# Schematic_Ebook_Reader_vFinal_v33.net
KiCad netlist of a schematic drawn in EAGLE
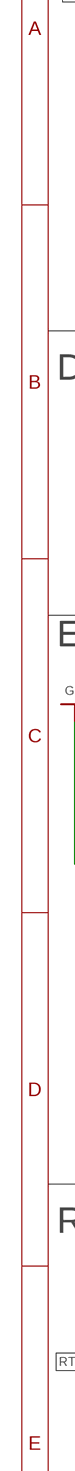
[diagram p0: schematic, sheet 1, part 1 of 2]
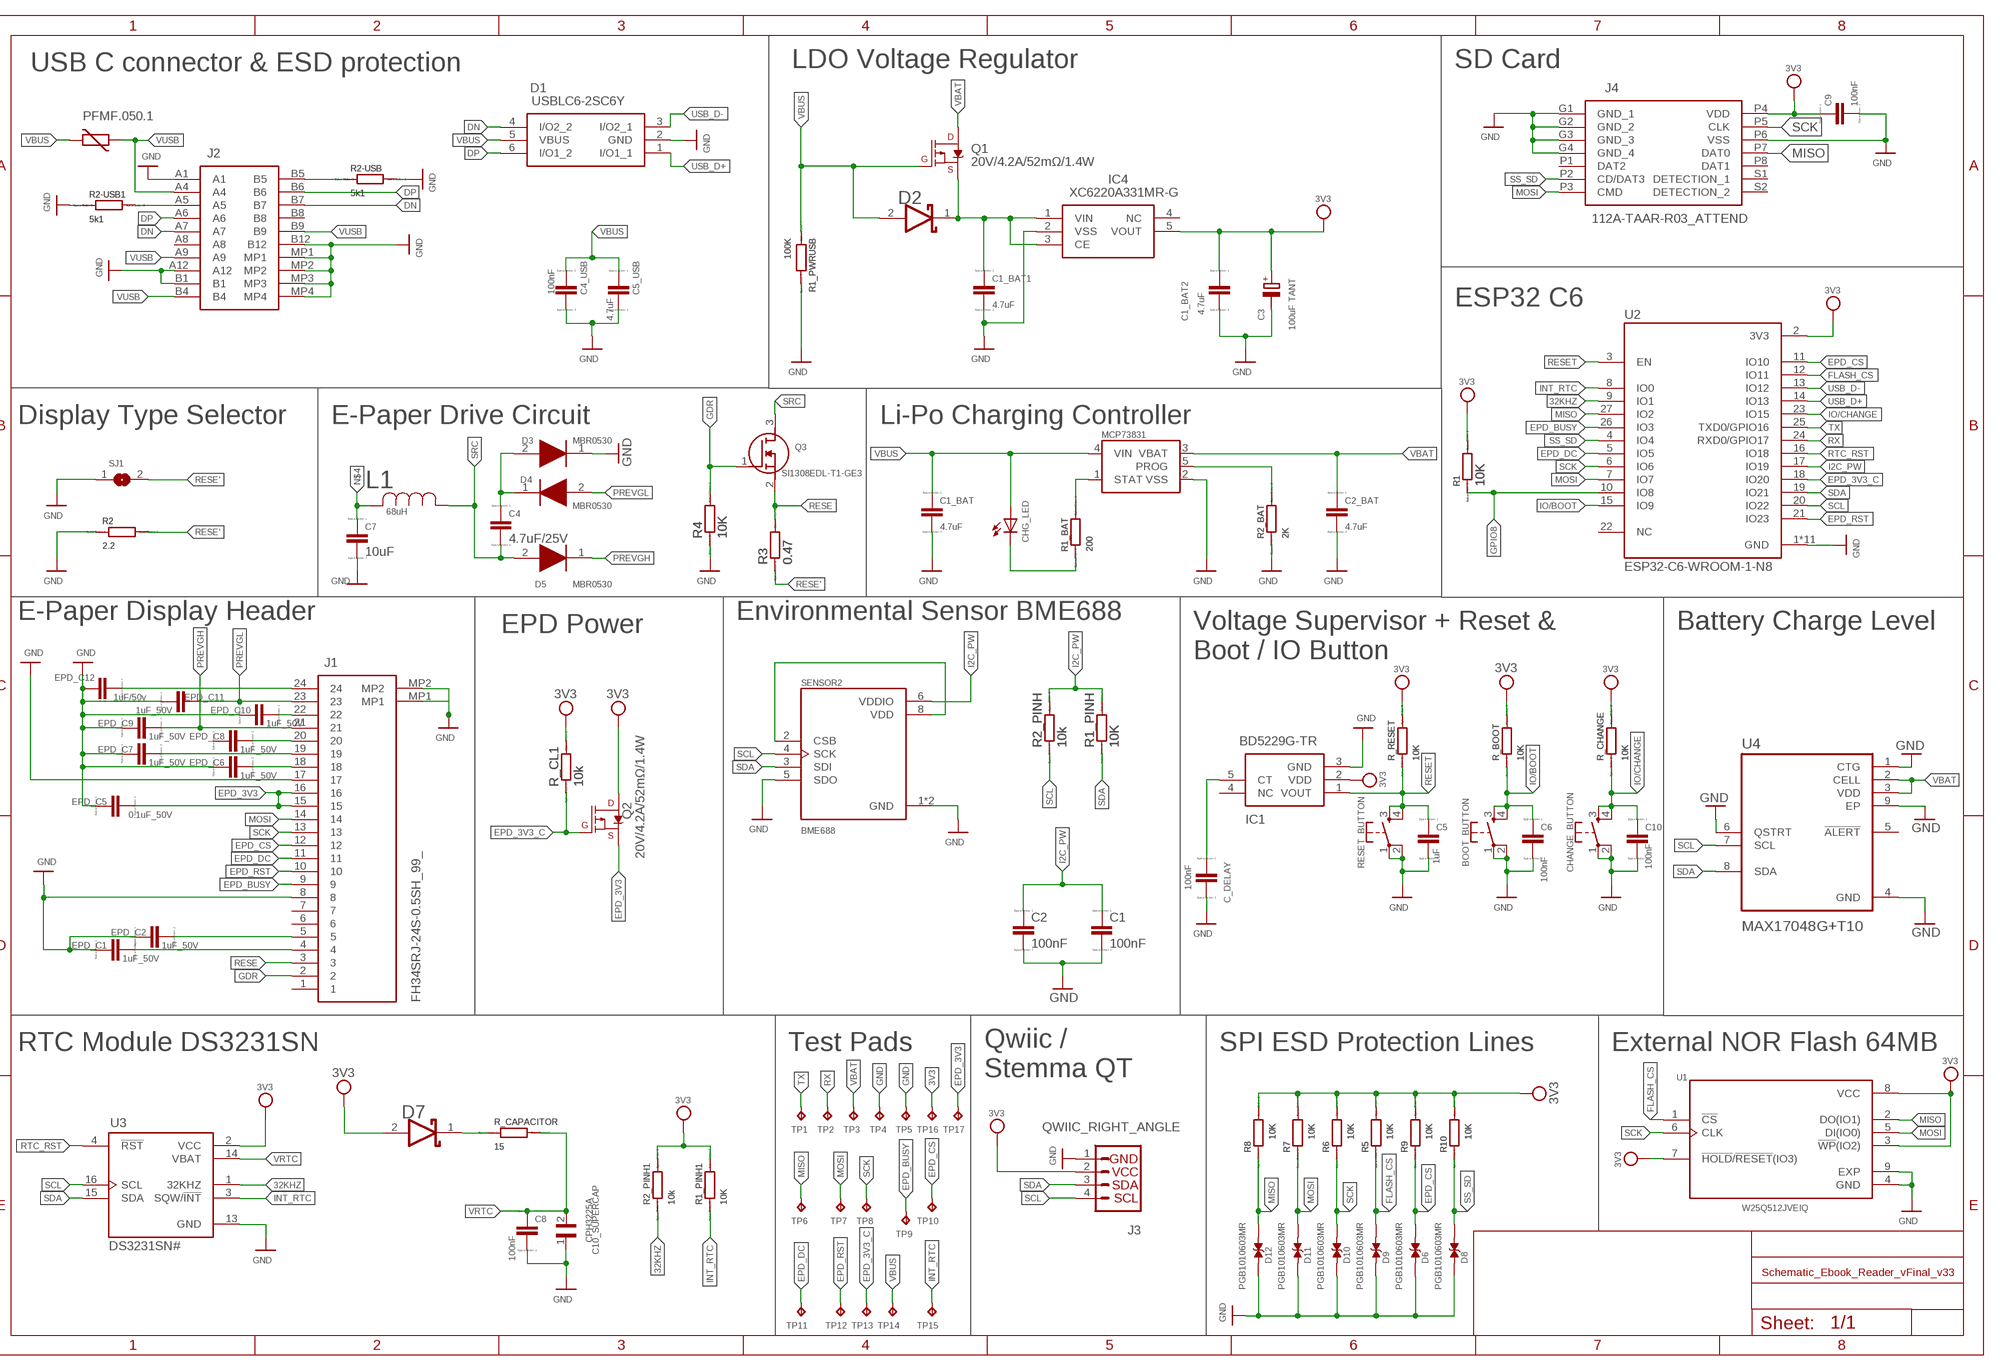
[diagram p1: schematic, sheet 1, part 2 of 2]

(export (version "E")
  (design (tool "Eeschema 10.0.6"))
  (components
    (comp (ref "BOOT_BUTTON")
      (value "BUTTON_CUSYOMV1")
      (footprint "eagle-import:MYBUTTON")
      (libsource (lib "eagle-import") (part "BUTTON_CUSYOMV1"))
    )
    (comp (ref "C1")
      (value "100nF")
      (footprint "eagle-import:EAGLE-LTSPICE_C0402")
      (libsource (lib "eagle-import") (part "EAGLE-LTSPICE_CC0402"))
    )
    (comp (ref "C1_BAT")
      (value "4.7uF")
      (footprint "eagle-import:EAGLE-LTSPICE_C0402")
      (libsource (lib "eagle-import") (part "EAGLE-LTSPICE_CC0402"))
    )
    (comp (ref "C1_BAT1")
      (value "4.7uF")
      (footprint "eagle-import:EAGLE-LTSPICE_C0402")
      (libsource (lib "eagle-import") (part "EAGLE-LTSPICE_CC0402"))
    )
    (comp (ref "C1_BAT2")
      (value "4.7uF")
      (footprint "eagle-import:EAGLE-LTSPICE_C0402")
      (libsource (lib "eagle-import") (part "EAGLE-LTSPICE_CC0402"))
    )
    (comp (ref "C2")
      (value "100nF")
      (footprint "eagle-import:EAGLE-LTSPICE_C0402")
      (libsource (lib "eagle-import") (part "EAGLE-LTSPICE_CC0402"))
    )
    (comp (ref "C2_BAT")
      (value "4.7uF")
      (footprint "eagle-import:EAGLE-LTSPICE_C0402")
      (libsource (lib "eagle-import") (part "EAGLE-LTSPICE_CC0402"))
    )
    (comp (ref "C3")
      (value "100uF TANT")
      (footprint "eagle-import:RCL_CT3528")
      (libsource (lib "eagle-import") (part "RCL_CPOL-EUCT3528"))
    )
    (comp (ref "C4")
      (value "4.7uF/25V")
      (footprint "eagle-import:EAGLE-LTSPICE_C0402")
      (libsource (lib "eagle-import") (part "EAGLE-LTSPICE_CC0402"))
    )
    (comp (ref "C4_USB")
      (value "100nF")
      (footprint "eagle-import:EAGLE-LTSPICE_C0402")
      (libsource (lib "eagle-import") (part "EAGLE-LTSPICE_CC0402"))
    )
    (comp (ref "C5")
      (value "1uF")
      (footprint "eagle-import:EAGLE-LTSPICE_C0402")
      (libsource (lib "eagle-import") (part "EAGLE-LTSPICE_CC0402"))
    )
    (comp (ref "C5_USB")
      (value "4.7uF")
      (footprint "eagle-import:EAGLE-LTSPICE_C0402")
      (libsource (lib "eagle-import") (part "EAGLE-LTSPICE_CC0402"))
    )
    (comp (ref "C6")
      (value "100nF")
      (footprint "eagle-import:EAGLE-LTSPICE_C0402")
      (libsource (lib "eagle-import") (part "EAGLE-LTSPICE_CC0402"))
    )
    (comp (ref "C7")
      (value "10uF")
      (footprint "eagle-import:EAGLE-LTSPICE_C0402")
      (libsource (lib "eagle-import") (part "EAGLE-LTSPICE_CC0402"))
    )
    (comp (ref "C8")
      (value "100nF")
      (footprint "eagle-import:EAGLE-LTSPICE_C0402")
      (libsource (lib "eagle-import") (part "EAGLE-LTSPICE_CC0402"))
    )
    (comp (ref "C9")
      (value "100nF")
      (footprint "eagle-import:EAGLE-LTSPICE_C0402")
      (libsource (lib "eagle-import") (part "EAGLE-LTSPICE_CC0402"))
    )
    (comp (ref "C10")
      (value "100nF")
      (footprint "eagle-import:EAGLE-LTSPICE_C0402")
      (libsource (lib "eagle-import") (part "EAGLE-LTSPICE_CC0402"))
    )
    (comp (ref "C10_SUPERCAP")
      (value "CPH3225A")
      (footprint "eagle-import:CAPCP3225X100N")
      (fields (field (name "MF") "Seiko Instruments"))
      (libsource (lib "eagle-import") (part "CPH3225A"))
    )
    (comp (ref "CHANGE_BUTTON")
      (value "BUTTON_CUSYOMV1")
      (footprint "eagle-import:MYBUTTON")
      (libsource (lib "eagle-import") (part "BUTTON_CUSYOMV1"))
    )
    (comp (ref "CHG_LED")
      (value "ADAFRUIT_LEDCHIP-LED0603")
      (footprint "eagle-import:ADAFRUIT_CHIP-LED0603")
      (libsource (lib "eagle-import") (part "ADAFRUIT_LEDCHIP-LED0603"))
    )
    (comp (ref "C_DELAY")
      (value "100nF")
      (footprint "eagle-import:EAGLE-LTSPICE_C0402")
      (libsource (lib "eagle-import") (part "EAGLE-LTSPICE_CC0402"))
    )
    (comp (ref "D1")
      (value "USBLC6-2SC6Y")
      (footprint "eagle-import:SOT95P280X145-6N")
      (fields (field (name "MF") "STMicroelectronics"))
      (libsource (lib "eagle-import") (part "USBLC6-2SC6Y"))
    )
    (comp (ref "D2")
      (value "ESP32_WROVER_AVX---SD0805S020S1R0_AVX_SD0805S020S1R0_0_0AVX_SD0805S020S1R0_0_0")
      (footprint "eagle-import:ESP32_WROVER_AVX---SD0805S020S1R0_AVX_SD0805S020S1R0_0")
      (fields
        (field (name "DIGIKEY_PART_NUMBER") "478-7800-1-ND")
        (field (name "MF") "AVX")
        (field (name "MOUSER_PART_NUMBER") "581-SD0805S020S1R0")
      )
      (libsource (lib "eagle-import") (part "ESP32_WROVER_AVX---SD0805S020S1R0_AVX_SD0805S020S1R0_0_0AVX_SD0805S020S1R0_0_0"))
    )
    (comp (ref "D3")
      (value "MBR0530")
      (footprint "eagle-import:SOD3716X135N")
      (fields (field (name "MF") "ON Semiconductor"))
      (libsource (lib "eagle-import") (part "MBR0530"))
    )
    (comp (ref "D4")
      (value "MBR0530")
      (footprint "eagle-import:SOD3716X135N")
      (fields (field (name "MF") "ON Semiconductor"))
      (libsource (lib "eagle-import") (part "MBR0530"))
    )
    (comp (ref "D5")
      (value "MBR0530")
      (footprint "eagle-import:SOD3716X135N")
      (fields (field (name "MF") "ON Semiconductor"))
      (libsource (lib "eagle-import") (part "MBR0530"))
    )
    (comp (ref "D6")
      (value "PGB1010603MR")
      (footprint "eagle-import:DIOC1608X36N")
      (fields (field (name "MF") "Littelfuse Inc."))
      (libsource (lib "eagle-import") (part "PGB1010603MR"))
    )
    (comp (ref "D7")
      (value "ESP32_WROVER_AVX---SD0805S020S1R0_AVX_SD0805S020S1R0_0_0AVX_SD0805S020S1R0_0_0")
      (footprint "eagle-import:ESP32_WROVER_AVX---SD0805S020S1R0_AVX_SD0805S020S1R0_0")
      (fields
        (field (name "DIGIKEY_PART_NUMBER") "478-7800-1-ND")
        (field (name "MF") "AVX")
        (field (name "MOUSER_PART_NUMBER") "581-SD0805S020S1R0")
      )
      (libsource (lib "eagle-import") (part "ESP32_WROVER_AVX---SD0805S020S1R0_AVX_SD0805S020S1R0_0_0AVX_SD0805S020S1R0_0_0"))
    )
    (comp (ref "D8")
      (value "PGB1010603MR")
      (footprint "eagle-import:DIOC1608X36N")
      (fields (field (name "MF") "Littelfuse Inc."))
      (libsource (lib "eagle-import") (part "PGB1010603MR"))
    )
    (comp (ref "D9")
      (value "PGB1010603MR")
      (footprint "eagle-import:DIOC1608X36N")
      (fields (field (name "MF") "Littelfuse Inc."))
      (libsource (lib "eagle-import") (part "PGB1010603MR"))
    )
    (comp (ref "D10")
      (value "PGB1010603MR")
      (footprint "eagle-import:DIOC1608X36N")
      (fields (field (name "MF") "Littelfuse Inc."))
      (libsource (lib "eagle-import") (part "PGB1010603MR"))
    )
    (comp (ref "D11")
      (value "PGB1010603MR")
      (footprint "eagle-import:DIOC1608X36N")
      (fields (field (name "MF") "Littelfuse Inc."))
      (libsource (lib "eagle-import") (part "PGB1010603MR"))
    )
    (comp (ref "D12")
      (value "PGB1010603MR")
      (footprint "eagle-import:DIOC1608X36N")
      (fields (field (name "MF") "Littelfuse Inc."))
      (libsource (lib "eagle-import") (part "PGB1010603MR"))
    )
    (comp (ref "EPD_C1")
      (value "1uF_50V")
      (footprint "eagle-import:EAGLE-LTSPICE_C0402")
      (libsource (lib "eagle-import") (part "EAGLE-LTSPICE_CC0402"))
    )
    (comp (ref "EPD_C2")
      (value "1uF_50V")
      (footprint "eagle-import:EAGLE-LTSPICE_C0402")
      (libsource (lib "eagle-import") (part "EAGLE-LTSPICE_CC0402"))
    )
    (comp (ref "EPD_C5")
      (value "0.1uF_50V")
      (footprint "eagle-import:EAGLE-LTSPICE_C0402")
      (libsource (lib "eagle-import") (part "EAGLE-LTSPICE_CC0402"))
    )
    (comp (ref "EPD_C6")
      (value "1uF_50V")
      (footprint "eagle-import:EAGLE-LTSPICE_C0402")
      (libsource (lib "eagle-import") (part "EAGLE-LTSPICE_CC0402"))
    )
    (comp (ref "EPD_C7")
      (value "1uF_50V")
      (footprint "eagle-import:EAGLE-LTSPICE_C0402")
      (libsource (lib "eagle-import") (part "EAGLE-LTSPICE_CC0402"))
    )
    (comp (ref "EPD_C8")
      (value "1uF_50V")
      (footprint "eagle-import:EAGLE-LTSPICE_C0402")
      (libsource (lib "eagle-import") (part "EAGLE-LTSPICE_CC0402"))
    )
    (comp (ref "EPD_C9")
      (value "1uF_50V")
      (footprint "eagle-import:EAGLE-LTSPICE_C0402")
      (libsource (lib "eagle-import") (part "EAGLE-LTSPICE_CC0402"))
    )
    (comp (ref "EPD_C10")
      (value "1uF_50V")
      (footprint "eagle-import:EAGLE-LTSPICE_C0402")
      (libsource (lib "eagle-import") (part "EAGLE-LTSPICE_CC0402"))
    )
    (comp (ref "EPD_C11")
      (value "1uF_50V")
      (footprint "eagle-import:EAGLE-LTSPICE_C0402")
      (libsource (lib "eagle-import") (part "EAGLE-LTSPICE_CC0402"))
    )
    (comp (ref "EPD_C12")
      (value "1uF/50v")
      (footprint "eagle-import:EAGLE-LTSPICE_C0402")
      (libsource (lib "eagle-import") (part "EAGLE-LTSPICE_CC0402"))
    )
    (comp (ref "IC1")
      (value "BD5229G-TR")
      (footprint "eagle-import:SOT95P280X125-5N")
      (fields (field (name "MOUSER_PART_NUMBER") "755-BD5229G-TR"))
      (libsource (lib "eagle-import") (part "BD5229G-TR"))
    )
    (comp (ref "IC4")
      (value "XC6220A331MR-G")
      (footprint "eagle-import:SOT95P280X120-5N")
      (fields (field (name "MOUSER_PART_NUMBER") "865-XC6220A331MR-G"))
      (libsource (lib "eagle-import") (part "XC6220A331MR-G"))
    )
    (comp (ref "J1")
      (value "FH34SRJ-24S-0.5SH_99_")
      (footprint "eagle-import:FH34SRJ24S05SH99")
      (fields
        (field (name "MANUFACTURER_PART_NUMBER") "FH34SRJ-24S-0.5SH(99)")
        (field (name "MOUSER_PART_NUMBER") "798-FH34SRJ24S05SH99")
      )
      (libsource (lib "eagle-import") (part "FH34SRJ-24S-0.5SH_99_"))
    )
    (comp (ref "J2")
      (value "SAMACSYS_PARTS_USB4110-GF-A")
      (footprint "eagle-import:SAMACSYS_PARTS_USB4110GFA")
      (fields
        (field (name "MANUFACTURER_PART_NUMBER") "USB4110-GF-A")
        (field (name "MOUSER_PART_NUMBER") "640-USB4110-GF-A")
      )
      (libsource (lib "eagle-import") (part "SAMACSYS_PARTS_USB4110-GF-A"))
    )
    (comp (ref "J3")
      (value "QWIIC_RIGHT_ANGLE")
      (footprint "eagle-import:JST04_1MM_RA")
      (libsource (lib "eagle-import") (part "QWIIC_CONNECTORJS-1MM"))
    )
    (comp (ref "J4")
      (value "112A-TAAR-R03_ATTEND")
      (footprint "eagle-import:112ATAARR03ATTEND")
      (fields (field (name "MANUFACTURER_PART_NUMBER") "112A-TAAR-R03 ATTEND"))
      (libsource (lib "eagle-import") (part "112A-TAAR-R03_ATTEND"))
    )
    (comp (ref "L1")
      (value "68uH")
      (footprint "eagle-import:IND_4828-WE-TPC_WRE")
      (fields
        (field (name "MANUFACTURER_PART_NUMBER") "744043680")
        (field (name "COPYRIGHT") "Copyright (C) 2024 Ultra Librarian. All rights reserved.")
      )
      (libsource (lib "eagle-import") (part "744043680IND_4828-WE-TPC_WRE"))
    )
    (comp (ref "MCP73831")
      (value "ESP32_WROVER_SPARKFUN-IC-POWER_MCP73831")
      (footprint "eagle-import:ESP32_WROVER_SPARKFUN-IC-POWER_SOT23-5")
      (libsource (lib "eagle-import") (part "ESP32_WROVER_SPARKFUN-IC-POWER_MCP73831"))
    )
    (comp (ref "PFMF.050.1")
      (value "ESP32C6_VARISTORCN1812")
      (footprint "eagle-import:ESP32C6_VARISTOR_CT_CN1812")
      (libsource (lib "eagle-import") (part "ESP32C6_VARISTORCN1812"))
    )
    (comp (ref "Q1")
      (value "20V/4.2A/52mΩ/1.4W")
      (footprint "eagle-import:ESP32_WROVER_SPARKFUN-DISCRETESEMI_SOT23-3")
      (libsource (lib "eagle-import") (part "ESP32_WROVER_SPARKFUN-DISCRETESEMI_MOSFET_PCH-DMG2305UX-7"))
    )
    (comp (ref "Q2")
      (value "20V/4.2A/52mΩ/1.4W")
      (footprint "eagle-import:ESP32_WROVER_SPARKFUN-DISCRETESEMI_SOT23-3")
      (libsource (lib "eagle-import") (part "ESP32_WROVER_SPARKFUN-DISCRETESEMI_MOSFET_PCH-DMG2305UX-7"))
    )
    (comp (ref "Q3")
      (value "SI1308EDL-T1-GE3")
      (footprint "eagle-import:SOT65P210X110-3N")
      (fields (field (name "MF") "Vishay Siliconix"))
      (libsource (lib "eagle-import") (part "SI1308EDL-T1-GE3"))
    )
    (comp (ref "R1")
      (value "10K")
      (footprint "eagle-import:ESP32_WROVER_EAGLE-LTSPICE_R0402")
      (libsource (lib "eagle-import") (part "ESP32_WROVER_EAGLE-LTSPICE_RR0402"))
    )
    (comp (ref "R1_BAT")
      (value "200")
      (footprint "eagle-import:ESP32_WROVER_EAGLE-LTSPICE_R0402")
      (libsource (lib "eagle-import") (part "ESP32_WROVER_EAGLE-LTSPICE_RR0402"))
    )
    (comp (ref "R1_PINH")
      (value "10K")
      (footprint "eagle-import:ESP32_WROVER_EAGLE-LTSPICE_R0402")
      (libsource (lib "eagle-import") (part "ESP32_WROVER_EAGLE-LTSPICE_RR0402"))
    )
    (comp (ref "R1_PINH1")
      (value "10K")
      (footprint "eagle-import:ESP32_WROVER_EAGLE-LTSPICE_R0402")
      (libsource (lib "eagle-import") (part "ESP32_WROVER_EAGLE-LTSPICE_RR0402"))
    )
    (comp (ref "R1_PWRUSB")
      (value "100K")
      (footprint "eagle-import:ESP32_WROVER_EAGLE-LTSPICE_R0402")
      (libsource (lib "eagle-import") (part "ESP32_WROVER_EAGLE-LTSPICE_RR0402"))
    )
    (comp (ref "R2")
      (value "2.2")
      (footprint "eagle-import:ESP32_WROVER_EAGLE-LTSPICE_R0402")
      (libsource (lib "eagle-import") (part "ESP32_WROVER_EAGLE-LTSPICE_RR0402"))
    )
    (comp (ref "R2-USB")
      (value "5k1")
      (footprint "eagle-import:ESP32_WROVER_EAGLE-LTSPICE_R0402")
      (libsource (lib "eagle-import") (part "ESP32_WROVER_EAGLE-LTSPICE_RR0402"))
    )
    (comp (ref "R2-USB1")
      (value "5k1")
      (footprint "eagle-import:ESP32_WROVER_EAGLE-LTSPICE_R0402")
      (libsource (lib "eagle-import") (part "ESP32_WROVER_EAGLE-LTSPICE_RR0402"))
    )
    (comp (ref "R2_BAT")
      (value "2K")
      (footprint "eagle-import:ESP32_WROVER_EAGLE-LTSPICE_R0402")
      (libsource (lib "eagle-import") (part "ESP32_WROVER_EAGLE-LTSPICE_RR0402"))
    )
    (comp (ref "R2_PINH")
      (value "10k")
      (footprint "eagle-import:ESP32_WROVER_EAGLE-LTSPICE_R0402")
      (libsource (lib "eagle-import") (part "ESP32_WROVER_EAGLE-LTSPICE_RR0402"))
    )
    (comp (ref "R2_PINH1")
      (value "10k")
      (footprint "eagle-import:ESP32_WROVER_EAGLE-LTSPICE_R0402")
      (libsource (lib "eagle-import") (part "ESP32_WROVER_EAGLE-LTSPICE_RR0402"))
    )
    (comp (ref "R3")
      (value "0.47")
      (footprint "eagle-import:ESP32_WROVER_EAGLE-LTSPICE_R0402")
      (libsource (lib "eagle-import") (part "ESP32_WROVER_EAGLE-LTSPICE_RR0402"))
    )
    (comp (ref "R4")
      (value "10K")
      (footprint "eagle-import:ESP32_WROVER_EAGLE-LTSPICE_R0402")
      (libsource (lib "eagle-import") (part "ESP32_WROVER_EAGLE-LTSPICE_RR0402"))
    )
    (comp (ref "R5")
      (value "10K")
      (footprint "eagle-import:ESP32_WROVER_EAGLE-LTSPICE_R0402")
      (libsource (lib "eagle-import") (part "ESP32_WROVER_EAGLE-LTSPICE_RR0402"))
    )
    (comp (ref "R6")
      (value "10K")
      (footprint "eagle-import:ESP32_WROVER_EAGLE-LTSPICE_R0402")
      (libsource (lib "eagle-import") (part "ESP32_WROVER_EAGLE-LTSPICE_RR0402"))
    )
    (comp (ref "R7")
      (value "10K")
      (footprint "eagle-import:ESP32_WROVER_EAGLE-LTSPICE_R0402")
      (libsource (lib "eagle-import") (part "ESP32_WROVER_EAGLE-LTSPICE_RR0402"))
    )
    (comp (ref "R8")
      (value "10K")
      (footprint "eagle-import:ESP32_WROVER_EAGLE-LTSPICE_R0402")
      (libsource (lib "eagle-import") (part "ESP32_WROVER_EAGLE-LTSPICE_RR0402"))
    )
    (comp (ref "R9")
      (value "10K")
      (footprint "eagle-import:ESP32_WROVER_EAGLE-LTSPICE_R0402")
      (libsource (lib "eagle-import") (part "ESP32_WROVER_EAGLE-LTSPICE_RR0402"))
    )
    (comp (ref "R10")
      (value "10K")
      (footprint "eagle-import:ESP32_WROVER_EAGLE-LTSPICE_R0402")
      (libsource (lib "eagle-import") (part "ESP32_WROVER_EAGLE-LTSPICE_RR0402"))
    )
    (comp (ref "RESET_BUTTON")
      (value "BUTTON_CUSYOMV1")
      (footprint "eagle-import:MYBUTTON")
      (libsource (lib "eagle-import") (part "BUTTON_CUSYOMV1"))
    )
    (comp (ref "R_BOOT")
      (value "10K")
      (footprint "eagle-import:ESP32_WROVER_EAGLE-LTSPICE_R0402")
      (libsource (lib "eagle-import") (part "ESP32_WROVER_EAGLE-LTSPICE_RR0402"))
    )
    (comp (ref "R_CAPACITOR")
      (value "15")
      (footprint "eagle-import:ESP32_WROVER_EAGLE-LTSPICE_R0402")
      (libsource (lib "eagle-import") (part "ESP32_WROVER_EAGLE-LTSPICE_RR0402"))
    )
    (comp (ref "R_CHANGE")
      (value "10K")
      (footprint "eagle-import:ESP32_WROVER_EAGLE-LTSPICE_R0402")
      (libsource (lib "eagle-import") (part "ESP32_WROVER_EAGLE-LTSPICE_RR0402"))
    )
    (comp (ref "R_CL1")
      (value "10k")
      (footprint "eagle-import:ESP32_WROVER_EAGLE-LTSPICE_R0402")
      (libsource (lib "eagle-import") (part "ESP32_WROVER_EAGLE-LTSPICE_RR0402"))
    )
    (comp (ref "R_RESET")
      (value "10K")
      (footprint "eagle-import:ESP32_WROVER_EAGLE-LTSPICE_R0402")
      (libsource (lib "eagle-import") (part "ESP32_WROVER_EAGLE-LTSPICE_RR0402"))
    )
    (comp (ref "SENSOR2")
      (value "BME688")
      (footprint "eagle-import:ESP32_WROVER_BME680_PSON80P300X300X100-8N")
      (fields (field (name "MF") "Bosch Sensortec") (field (name "MP") "BME680"))
      (libsource (lib "eagle-import") (part "ESP32_WROVER_BME680_BME680"))
    )
    (comp (ref "SJ1") (value "SJ") (footprint "eagle-import:SJ") (libsource (lib "eagle-import") (part "SJ")))
    (comp (ref "TP1")
      (value "TPTP20R")
      (footprint "eagle-import:TP20R")
      (libsource (lib "eagle-import") (part "TPTP20R"))
    )
    (comp (ref "TP2")
      (value "TPTP20R")
      (footprint "eagle-import:TP20R")
      (libsource (lib "eagle-import") (part "TPTP20R"))
    )
    (comp (ref "TP3")
      (value "TPTP20R")
      (footprint "eagle-import:TP20R")
      (libsource (lib "eagle-import") (part "TPTP20R"))
    )
    (comp (ref "TP4")
      (value "TPTP20R")
      (footprint "eagle-import:TP20R")
      (libsource (lib "eagle-import") (part "TPTP20R"))
    )
    (comp (ref "TP5")
      (value "TPTP20R")
      (footprint "eagle-import:TP20R")
      (libsource (lib "eagle-import") (part "TPTP20R"))
    )
    (comp (ref "TP6")
      (value "TPTP20R")
      (footprint "eagle-import:TP20R")
      (libsource (lib "eagle-import") (part "TPTP20R"))
    )
    (comp (ref "TP7")
      (value "TPTP20R")
      (footprint "eagle-import:TP20R")
      (libsource (lib "eagle-import") (part "TPTP20R"))
    )
    (comp (ref "TP8")
      (value "TPTP20R")
      (footprint "eagle-import:TP20R")
      (libsource (lib "eagle-import") (part "TPTP20R"))
    )
    (comp (ref "TP9")
      (value "TPTP20R")
      (footprint "eagle-import:TP20R")
      (libsource (lib "eagle-import") (part "TPTP20R"))
    )
    (comp (ref "TP10")
      (value "TPTP20R")
      (footprint "eagle-import:TP20R")
      (libsource (lib "eagle-import") (part "TPTP20R"))
    )
    (comp (ref "TP11")
      (value "TPTP20R")
      (footprint "eagle-import:TP20R")
      (libsource (lib "eagle-import") (part "TPTP20R"))
    )
    (comp (ref "TP12")
      (value "TPTP20R")
      (footprint "eagle-import:TP20R")
      (libsource (lib "eagle-import") (part "TPTP20R"))
    )
    (comp (ref "TP13")
      (value "TPTP20R")
      (footprint "eagle-import:TP20R")
      (libsource (lib "eagle-import") (part "TPTP20R"))
    )
    (comp (ref "TP14")
      (value "TPTP20R")
      (footprint "eagle-import:TP20R")
      (libsource (lib "eagle-import") (part "TPTP20R"))
    )
    (comp (ref "TP15")
      (value "TPTP20R")
      (footprint "eagle-import:TP20R")
      (libsource (lib "eagle-import") (part "TPTP20R"))
    )
    (comp (ref "TP16")
      (value "TPTP20R")
      (footprint "eagle-import:TP20R")
      (libsource (lib "eagle-import") (part "TPTP20R"))
    )
    (comp (ref "TP17")
      (value "TPTP20R")
      (footprint "eagle-import:TP20R")
      (libsource (lib "eagle-import") (part "TPTP20R"))
    )
    (comp (ref "U1")
      (value "W25Q512JVEIQ")
      (footprint "eagle-import:SON127P600X800X80-9N")
      (fields (field (name "MF") "Winbond Electronics"))
      (libsource (lib "eagle-import") (part "W25Q512JVEIQ"))
    )
    (comp (ref "U2")
      (value "ESP32-C6-WROOM-1-N8")
      (footprint "eagle-import:XCVR_ESP32-C6-WROOM-1-N8")
      (fields (field (name "MF") "Espressif Systems"))
      (libsource (lib "eagle-import") (part "ESP32-C6-WROOM-1-N8"))
    )
    (comp (ref "U3")
      (value "DS3231SN#")
      (footprint "eagle-import:SOIC127P1032X265-16N")
      (fields (field (name "MF") "Analog Devices"))
      (libsource (lib "eagle-import") (part "DS3231SN#"))
    )
    (comp (ref "U4")
      (value "MAX17048G+T10")
      (footprint "eagle-import:SON50P200X200X80-9N")
      (fields (field (name "MF") "Analog Devices"))
      (libsource (lib "eagle-import") (part "MAX17048G+T10"))
    )
  )
  (nets
    (net (code "1") (name "3V3") (class "Default")
      (node (ref "C1_BAT2") (pin "1") (pinfunction "1_1") (pintype "passive"))
      (node (ref "C3") (pin "+") (pinfunction "+_+") (pintype "passive"))
      (node (ref "C9") (pin "1") (pinfunction "1_1") (pintype "passive"))
      (node (ref "D7") (pin "2") (pinfunction "ANODE_2") (pintype "bidirectional"))
      (node (ref "IC1") (pin "2") (pinfunction "VDD_2") (pintype "bidirectional"))
      (node (ref "IC4") (pin "5") (pinfunction "VOUT_5") (pintype "bidirectional"))
      (node (ref "J3") (pin "2") (pinfunction "2_2") (pintype "power_in"))
      (node (ref "J4") (pin "P4") (pinfunction "VDD_P4") (pintype "bidirectional"))
      (node (ref "Q2") (pin "3") (pinfunction "D_3") (pintype "bidirectional"))
      (node (ref "R1") (pin "2") (pinfunction "2_2") (pintype "passive"))
      (node (ref "R10") (pin "2") (pinfunction "2_2") (pintype "passive"))
      (node (ref "R1_PINH1") (pin "2") (pinfunction "2_2") (pintype "passive"))
      (node (ref "R2_PINH1") (pin "2") (pinfunction "2_2") (pintype "passive"))
      (node (ref "R5") (pin "2") (pinfunction "2_2") (pintype "passive"))
      (node (ref "R6") (pin "2") (pinfunction "2_2") (pintype "passive"))
      (node (ref "R7") (pin "2") (pinfunction "2_2") (pintype "passive"))
      (node (ref "R8") (pin "2") (pinfunction "2_2") (pintype "passive"))
      (node (ref "R9") (pin "2") (pinfunction "2_2") (pintype "passive"))
      (node (ref "R_BOOT") (pin "2") (pinfunction "2_2") (pintype "passive"))
      (node (ref "R_CHANGE") (pin "2") (pinfunction "2_2") (pintype "passive"))
      (node (ref "R_CL1") (pin "2") (pinfunction "2_2") (pintype "passive"))
      (node (ref "R_RESET") (pin "2") (pinfunction "2_2") (pintype "passive"))
      (node (ref "TP16") (pin "TP") (pinfunction "TP_TP") (pintype "input"))
      (node (ref "U1") (pin "3") (pinfunction "~{WP}(IO2)_3") (pintype "bidirectional"))
      (node (ref "U1") (pin "7") (pinfunction "~{HOLD}/~{RESET}(IO3)_7") (pintype "bidirectional"))
      (node (ref "U1") (pin "8") (pinfunction "VCC_8") (pintype "power_in"))
      (node (ref "U2") (pin "2") (pinfunction "3V3_2") (pintype "power_in"))
      (node (ref "U3") (pin "2") (pinfunction "VCC_2") (pintype "power_in"))
    )
    (net (code "2") (name "32KHZ") (class "Default")
      (node (ref "R2_PINH1") (pin "1") (pinfunction "1_1") (pintype "passive"))
      (node (ref "U2") (pin "9") (pinfunction "IO1_9") (pintype "bidirectional"))
      (node (ref "U3") (pin "1") (pinfunction "32KHZ_1") (pintype "output"))
    )
    (net (code "3") (name "DN") (class "Default")
      (node (ref "D1") (pin "4") (pinfunction "I/O2_2_4") (pintype "bidirectional"))
      (node (ref "J2") (pin "A7") (pinfunction "A7_A7") (pintype "bidirectional"))
      (node (ref "J2") (pin "B7") (pinfunction "B7_B7") (pintype "bidirectional"))
    )
    (net (code "4") (name "DP") (class "Default")
      (node (ref "D1") (pin "6") (pinfunction "I/O1_2_6") (pintype "bidirectional"))
      (node (ref "J2") (pin "A6") (pinfunction "A6_A6") (pintype "bidirectional"))
      (node (ref "J2") (pin "B6") (pinfunction "B6_B6") (pintype "bidirectional"))
    )
    (net (code "5") (name "EPD_3V3") (class "Default")
      (node (ref "EPD_C5") (pin "2") (pinfunction "2_2") (pintype "passive"))
      (node (ref "J1") (pin "15") (pinfunction "15_15") (pintype "bidirectional"))
      (node (ref "J1") (pin "16") (pinfunction "16_16") (pintype "bidirectional"))
      (node (ref "Q2") (pin "2") (pinfunction "S_2") (pintype "bidirectional"))
      (node (ref "TP17") (pin "TP") (pinfunction "TP_TP") (pintype "input"))
    )
    (net (code "6") (name "EPD_3V3_C") (class "Default")
      (node (ref "Q2") (pin "1") (pinfunction "G_1") (pintype "bidirectional"))
      (node (ref "R_CL1") (pin "1") (pinfunction "1_1") (pintype "passive"))
      (node (ref "TP13") (pin "TP") (pinfunction "TP_TP") (pintype "input"))
      (node (ref "U2") (pin "18") (pinfunction "IO20_18") (pintype "bidirectional"))
    )
    (net (code "7") (name "EPD_BUSY") (class "Default")
      (node (ref "J1") (pin "9") (pinfunction "9_9") (pintype "bidirectional"))
      (node (ref "TP9") (pin "TP") (pinfunction "TP_TP") (pintype "input"))
      (node (ref "U2") (pin "26") (pinfunction "IO3_26") (pintype "bidirectional"))
    )
    (net (code "8") (name "EPD_CS") (class "Default")
      (node (ref "D6") (pin "2") (pinfunction "2_2") (pintype "passive"))
      (node (ref "J1") (pin "12") (pinfunction "12_12") (pintype "bidirectional"))
      (node (ref "R9") (pin "1") (pinfunction "1_1") (pintype "passive"))
      (node (ref "TP10") (pin "TP") (pinfunction "TP_TP") (pintype "input"))
      (node (ref "U2") (pin "11") (pinfunction "IO10_11") (pintype "bidirectional"))
    )
    (net (code "9") (name "EPD_DC") (class "Default")
      (node (ref "J1") (pin "11") (pinfunction "11_11") (pintype "bidirectional"))
      (node (ref "TP11") (pin "TP") (pinfunction "TP_TP") (pintype "input"))
      (node (ref "U2") (pin "5") (pinfunction "IO5_5") (pintype "bidirectional"))
    )
    (net (code "10") (name "EPD_RST") (class "Default")
      (node (ref "J1") (pin "10") (pinfunction "10_10") (pintype "bidirectional"))
      (node (ref "TP12") (pin "TP") (pinfunction "TP_TP") (pintype "input"))
      (node (ref "U2") (pin "21") (pinfunction "IO23_21") (pintype "bidirectional"))
    )
    (net (code "11") (name "FLASH_CS") (class "Default")
      (node (ref "D9") (pin "2") (pinfunction "2_2") (pintype "passive"))
      (node (ref "R5") (pin "1") (pinfunction "1_1") (pintype "passive"))
      (node (ref "U1") (pin "1") (pinfunction "~{CS}_1") (pintype "input"))
      (node (ref "U2") (pin "12") (pinfunction "IO11_12") (pintype "bidirectional"))
    )
    (net (code "12") (name "GDR") (class "Default")
      (node (ref "J1") (pin "2") (pinfunction "2_2") (pintype "bidirectional"))
      (node (ref "Q3") (pin "1") (pinfunction "G_1") (pintype "bidirectional"))
      (node (ref "R4") (pin "2") (pinfunction "2_2") (pintype "passive"))
    )
    (net (code "13") (name "GND") (class "Default")
      (node (ref "BOOT_BUTTON") (pin "1") (pinfunction "1_1") (pintype "passive"))
      (node (ref "BOOT_BUTTON") (pin "2") (pinfunction "2_2") (pintype "passive"))
      (node (ref "C1") (pin "2") (pinfunction "2_2") (pintype "passive"))
      (node (ref "C10") (pin "2") (pinfunction "2_2") (pintype "passive"))
      (node (ref "C10_SUPERCAP") (pin "1") (pinfunction "1_1") (pintype "passive"))
      (node (ref "C1_BAT") (pin "2") (pinfunction "2_2") (pintype "passive"))
      (node (ref "C1_BAT1") (pin "2") (pinfunction "2_2") (pintype "passive"))
      (node (ref "C1_BAT2") (pin "2") (pinfunction "2_2") (pintype "passive"))
      (node (ref "C2") (pin "2") (pinfunction "2_2") (pintype "passive"))
      (node (ref "C2_BAT") (pin "2") (pinfunction "2_2") (pintype "passive"))
      (node (ref "C3") (pin "-") (pinfunction "-_-") (pintype "passive"))
      (node (ref "C4_USB") (pin "2") (pinfunction "2_2") (pintype "passive"))
      (node (ref "C5") (pin "2") (pinfunction "2_2") (pintype "passive"))
      (node (ref "C5_USB") (pin "2") (pinfunction "2_2") (pintype "passive"))
      (node (ref "C6") (pin "2") (pinfunction "2_2") (pintype "passive"))
      (node (ref "C7") (pin "2") (pinfunction "2_2") (pintype "passive"))
      (node (ref "C8") (pin "2") (pinfunction "2_2") (pintype "passive"))
      (node (ref "C9") (pin "2") (pinfunction "2_2") (pintype "passive"))
      (node (ref "CHANGE_BUTTON") (pin "1") (pinfunction "1_1") (pintype "passive"))
      (node (ref "CHANGE_BUTTON") (pin "2") (pinfunction "2_2") (pintype "passive"))
      (node (ref "C_DELAY") (pin "2") (pinfunction "2_2") (pintype "passive"))
      (node (ref "D1") (pin "2") (pinfunction "GND_2") (pintype "bidirectional"))
      (node (ref "D10") (pin "1") (pinfunction "1_1") (pintype "passive"))
      (node (ref "D11") (pin "1") (pinfunction "1_1") (pintype "passive"))
      (node (ref "D12") (pin "1") (pinfunction "1_1") (pintype "passive"))
      (node (ref "D3") (pin "1") (pinfunction "K_1") (pintype "bidirectional"))
      (node (ref "D6") (pin "1") (pinfunction "1_1") (pintype "passive"))
      (node (ref "D8") (pin "1") (pinfunction "1_1") (pintype "passive"))
      (node (ref "D9") (pin "1") (pinfunction "1_1") (pintype "passive"))
      (node (ref "EPD_C1") (pin "1") (pinfunction "1_1") (pintype "passive"))
      (node (ref "EPD_C10") (pin "1") (pinfunction "1_1") (pintype "passive"))
      (node (ref "EPD_C11") (pin "1") (pinfunction "1_1") (pintype "passive"))
      (node (ref "EPD_C12") (pin "1") (pinfunction "1_1") (pintype "passive"))
      (node (ref "EPD_C2") (pin "1") (pinfunction "1_1") (pintype "passive"))
      (node (ref "EPD_C5") (pin "1") (pinfunction "1_1") (pintype "passive"))
      (node (ref "EPD_C6") (pin "1") (pinfunction "1_1") (pintype "passive"))
      (node (ref "EPD_C7") (pin "1") (pinfunction "1_1") (pintype "passive"))
      (node (ref "EPD_C9") (pin "1") (pinfunction "1_1") (pintype "passive"))
      (node (ref "IC1") (pin "3") (pinfunction "GND_3") (pintype "bidirectional"))
      (node (ref "IC4") (pin "2") (pinfunction "VSS_2") (pintype "bidirectional"))
      (node (ref "J1") (pin "17") (pinfunction "17_17") (pintype "bidirectional"))
      (node (ref "J1") (pin "8") (pinfunction "8_8") (pintype "bidirectional"))
      (node (ref "J1") (pin "MP1") (pinfunction "MP1_MP1") (pintype "bidirectional"))
      (node (ref "J1") (pin "MP2") (pinfunction "MP2_MP2") (pintype "bidirectional"))
      (node (ref "J2") (pin "A1") (pinfunction "A1_A1") (pintype "bidirectional"))
      (node (ref "J2") (pin "A12") (pinfunction "A12_A12") (pintype "bidirectional"))
      (node (ref "J2") (pin "B1") (pinfunction "B1_B1") (pintype "bidirectional"))
      (node (ref "J2") (pin "B12") (pinfunction "B12_B12") (pintype "bidirectional"))
      (node (ref "J2") (pin "MP1") (pinfunction "MP1_MP1") (pintype "bidirectional"))
      (node (ref "J2") (pin "MP2") (pinfunction "MP2_MP2") (pintype "bidirectional"))
      (node (ref "J2") (pin "MP3") (pinfunction "MP3_MP3") (pintype "bidirectional"))
      (node (ref "J2") (pin "MP4") (pinfunction "MP4_MP4") (pintype "bidirectional"))
      (node (ref "J3") (pin "1") (pinfunction "1_1") (pintype "power_in"))
      (node (ref "J4") (pin "G1") (pinfunction "GND_1_G1") (pintype "bidirectional"))
      (node (ref "J4") (pin "G2") (pinfunction "GND_2_G2") (pintype "bidirectional"))
      (node (ref "J4") (pin "G3") (pinfunction "GND_3_G3") (pintype "bidirectional"))
      (node (ref "J4") (pin "G4") (pinfunction "GND_4_G4") (pintype "bidirectional"))
      (node (ref "J4") (pin "P6") (pinfunction "VSS_P6") (pintype "bidirectional"))
      (node (ref "MCP73831") (pin "2") (pinfunction "VSS_2") (pintype "power_in"))
      (node (ref "R1_PWRUSB") (pin "2") (pinfunction "2_2") (pintype "passive"))
      (node (ref "R2") (pin "1") (pinfunction "1_1") (pintype "passive"))
      (node (ref "R2-USB") (pin "2") (pinfunction "2_2") (pintype "passive"))
      (node (ref "R2-USB1") (pin "1") (pinfunction "1_1") (pintype "passive"))
      (node (ref "R2_BAT") (pin "1") (pinfunction "1_1") (pintype "passive"))
      (node (ref "R4") (pin "1") (pinfunction "1_1") (pintype "passive"))
      (node (ref "RESET_BUTTON") (pin "1") (pinfunction "1_1") (pintype "passive"))
      (node (ref "RESET_BUTTON") (pin "2") (pinfunction "2_2") (pintype "passive"))
      (node (ref "SENSOR2") (pin "1") (pinfunction "GND_1") (pintype "power_in"))
      (node (ref "SENSOR2") (pin "5") (pinfunction "SDO_5") (pintype "bidirectional"))
      (node (ref "SENSOR2") (pin "7") (pinfunction "GND_7") (pintype "power_in"))
      (node (ref "SJ1") (pin "1") (pinfunction "1_1") (pintype "passive"))
      (node (ref "TP4") (pin "TP") (pinfunction "TP_TP") (pintype "input"))
      (node (ref "TP5") (pin "TP") (pinfunction "TP_TP") (pintype "input"))
      (node (ref "U1") (pin "4") (pinfunction "GND_4") (pintype "power_in"))
      (node (ref "U1") (pin "9") (pinfunction "EXP_9") (pintype "passive"))
      (node (ref "U2") (pin "1") (pinfunction "GND_1") (pintype "power_in"))
      (node (ref "U2") (pin "28") (pinfunction "GND_28") (pintype "power_in"))
      (node (ref "U2") (pin "29_1") (pinfunction "GND_29_1") (pintype "power_in"))
      (node (ref "U2") (pin "29_2") (pinfunction "GND_29_2") (pintype "power_in"))
      (node (ref "U2") (pin "29_3") (pinfunction "GND_29_3") (pintype "power_in"))
      (node (ref "U2") (pin "29_4") (pinfunction "GND_29_4") (pintype "power_in"))
      (node (ref "U2") (pin "29_5") (pinfunction "GND_29_5") (pintype "power_in"))
      (node (ref "U2") (pin "29_6") (pinfunction "GND_29_6") (pintype "power_in"))
      (node (ref "U2") (pin "29_7") (pinfunction "GND_29_7") (pintype "power_in"))
      (node (ref "U2") (pin "29_8") (pinfunction "GND_29_8") (pintype "power_in"))
      (node (ref "U2") (pin "29_9") (pinfunction "GND_29_9") (pintype "power_in"))
      (node (ref "U3") (pin "13") (pinfunction "GND_13") (pintype "power_in"))
      (node (ref "U4") (pin "1") (pinfunction "CTG_1") (pintype "power_in"))
      (node (ref "U4") (pin "4") (pinfunction "GND_4") (pintype "power_in"))
      (node (ref "U4") (pin "6") (pinfunction "QSTRT_6") (pintype "input"))
      (node (ref "U4") (pin "9") (pinfunction "EP_9") (pintype "power_in"))
    )
    (net (code "14") (name "GPIO8") (class "Default")
      (node (ref "R1") (pin "1") (pinfunction "1_1") (pintype "passive"))
      (node (ref "U2") (pin "10") (pinfunction "IO8_10") (pintype "bidirectional"))
    )
    (net (code "15") (name "I2C_PW") (class "Default")
      (node (ref "C1") (pin "1") (pinfunction "1_1") (pintype "passive"))
      (node (ref "C2") (pin "1") (pinfunction "1_1") (pintype "passive"))
      (node (ref "R1_PINH") (pin "2") (pinfunction "2_2") (pintype "passive"))
      (node (ref "R2_PINH") (pin "2") (pinfunction "2_2") (pintype "passive"))
      (node (ref "SENSOR2") (pin "6") (pinfunction "VDDIO_6") (pintype "power_in"))
      (node (ref "U2") (pin "17") (pinfunction "IO19_17") (pintype "bidirectional"))
    )
    (net (code "16") (name "INT_RTC") (class "Default")
      (node (ref "R1_PINH1") (pin "1") (pinfunction "1_1") (pintype "passive"))
      (node (ref "TP15") (pin "TP") (pinfunction "TP_TP") (pintype "input"))
      (node (ref "U2") (pin "8") (pinfunction "IO0_8") (pintype "bidirectional"))
      (node (ref "U3") (pin "3") (pinfunction "SQW/~{INT}_3") (pintype "output"))
    )
    (net (code "17") (name "IO{slash}BOOT") (class "Default")
      (node (ref "BOOT_BUTTON") (pin "3") (pinfunction "3_3") (pintype "passive"))
      (node (ref "BOOT_BUTTON") (pin "4") (pinfunction "4_4") (pintype "passive"))
      (node (ref "C6") (pin "1") (pinfunction "1_1") (pintype "passive"))
      (node (ref "R_BOOT") (pin "1") (pinfunction "1_1") (pintype "passive"))
      (node (ref "U2") (pin "15") (pinfunction "IO9_15") (pintype "bidirectional"))
    )
    (net (code "18") (name "IO{slash}CHANGE") (class "Default")
      (node (ref "C10") (pin "1") (pinfunction "1_1") (pintype "passive"))
      (node (ref "CHANGE_BUTTON") (pin "3") (pinfunction "3_3") (pintype "passive"))
      (node (ref "CHANGE_BUTTON") (pin "4") (pinfunction "4_4") (pintype "passive"))
      (node (ref "R_CHANGE") (pin "1") (pinfunction "1_1") (pintype "passive"))
      (node (ref "U2") (pin "23") (pinfunction "IO15_23") (pintype "bidirectional"))
    )
    (net (code "19") (name "MISO") (class "Default")
      (node (ref "D12") (pin "2") (pinfunction "2_2") (pintype "passive"))
      (node (ref "J4") (pin "P7") (pinfunction "DAT0_P7") (pintype "bidirectional"))
      (node (ref "R8") (pin "1") (pinfunction "1_1") (pintype "passive"))
      (node (ref "TP6") (pin "TP") (pinfunction "TP_TP") (pintype "input"))
      (node (ref "U1") (pin "2") (pinfunction "DO(IO1)_2") (pintype "bidirectional"))
      (node (ref "U2") (pin "27") (pinfunction "IO2_27") (pintype "bidirectional"))
    )
    (net (code "20") (name "MOSI") (class "Default")
      (node (ref "D11") (pin "2") (pinfunction "2_2") (pintype "passive"))
      (node (ref "J1") (pin "14") (pinfunction "14_14") (pintype "bidirectional"))
      (node (ref "J4") (pin "P3") (pinfunction "CMD_P3") (pintype "bidirectional"))
      (node (ref "R7") (pin "1") (pinfunction "1_1") (pintype "passive"))
      (node (ref "TP7") (pin "TP") (pinfunction "TP_TP") (pintype "input"))
      (node (ref "U1") (pin "5") (pinfunction "DI(IO0)_5") (pintype "bidirectional"))
      (node (ref "U2") (pin "7") (pinfunction "IO7_7") (pintype "bidirectional"))
    )
    (net (code "21") (name "N$4") (class "Default")
      (node (ref "C7") (pin "1") (pinfunction "1_1") (pintype "passive"))
      (node (ref "L1") (pin "2") (pinfunction "2_2") (pintype "passive"))
    )
    (net (code "22") (name "Net-(CHG_LED-PadC)") (class "Default")
      (node (ref "CHG_LED") (pin "C") (pinfunction "C_C") (pintype "passive"))
      (node (ref "R1_BAT") (pin "1") (pinfunction "1_1") (pintype "passive"))
    )
    (net (code "23") (name "Net-(D2-CATHODE)") (class "Default")
      (node (ref "C1_BAT1") (pin "1") (pinfunction "1_1") (pintype "passive"))
      (node (ref "D2") (pin "1") (pinfunction "CATHODE_1") (pintype "bidirectional"))
      (node (ref "IC4") (pin "1") (pinfunction "VIN_1") (pintype "bidirectional"))
      (node (ref "IC4") (pin "3") (pinfunction "CE_3") (pintype "bidirectional"))
      (node (ref "Q1") (pin "2") (pinfunction "S_2") (pintype "bidirectional"))
    )
    (net (code "24") (name "Net-(D3-A)") (class "Default")
      (node (ref "C4") (pin "1") (pinfunction "1_1") (pintype "passive"))
      (node (ref "D3") (pin "2") (pinfunction "A_2") (pintype "bidirectional"))
      (node (ref "D4") (pin "1") (pinfunction "K_1") (pintype "bidirectional"))
    )
    (net (code "25") (name "Net-(D7-CATHODE)") (class "Default")
      (node (ref "D7") (pin "1") (pinfunction "CATHODE_1") (pintype "bidirectional"))
      (node (ref "R_CAPACITOR") (pin "1") (pinfunction "1_1") (pintype "passive"))
    )
    (net (code "26") (name "Net-(EPD_C1-Pad2)") (class "Default")
      (node (ref "EPD_C1") (pin "2") (pinfunction "2_2") (pintype "passive"))
      (node (ref "J1") (pin "4") (pinfunction "4_4") (pintype "bidirectional"))
    )
    (net (code "27") (name "Net-(EPD_C2-Pad2)") (class "Default")
      (node (ref "EPD_C2") (pin "2") (pinfunction "2_2") (pintype "passive"))
      (node (ref "J1") (pin "5") (pinfunction "5_5") (pintype "bidirectional"))
    )
    (net (code "28") (name "Net-(EPD_C6-Pad2)") (class "Default")
      (node (ref "EPD_C6") (pin "2") (pinfunction "2_2") (pintype "passive"))
      (node (ref "J1") (pin "18") (pinfunction "18_18") (pintype "bidirectional"))
    )
    (net (code "29") (name "Net-(EPD_C7-Pad2)") (class "Default")
      (node (ref "EPD_C7") (pin "2") (pinfunction "2_2") (pintype "passive"))
      (node (ref "J1") (pin "19") (pinfunction "19_19") (pintype "bidirectional"))
    )
    (net (code "30") (name "Net-(EPD_C8-Pad2)") (class "Default")
      (node (ref "EPD_C8") (pin "2") (pinfunction "2_2") (pintype "passive"))
      (node (ref "J1") (pin "20") (pinfunction "20_20") (pintype "bidirectional"))
    )
    (net (code "31") (name "Net-(EPD_C10-Pad2)") (class "Default")
      (node (ref "EPD_C10") (pin "2") (pinfunction "2_2") (pintype "passive"))
      (node (ref "J1") (pin "22") (pinfunction "22_22") (pintype "bidirectional"))
    )
    (net (code "32") (name "Net-(EPD_C12-Pad2)") (class "Default")
      (node (ref "EPD_C12") (pin "2") (pinfunction "2_2") (pintype "passive"))
      (node (ref "J1") (pin "24") (pinfunction "24_24") (pintype "bidirectional"))
    )
    (net (code "33") (name "Net-(IC1-CT)") (class "Default")
      (node (ref "C_DELAY") (pin "1") (pinfunction "1_1") (pintype "passive"))
      (node (ref "IC1") (pin "5") (pinfunction "CT_5") (pintype "bidirectional"))
    )
    (net (code "34") (name "Net-(J2-PadA5)") (class "Default")
      (node (ref "J2") (pin "A5") (pinfunction "A5_A5") (pintype "bidirectional"))
      (node (ref "R2-USB1") (pin "2") (pinfunction "2_2") (pintype "passive"))
    )
    (net (code "35") (name "Net-(J2-PadB5)") (class "Default")
      (node (ref "J2") (pin "B5") (pinfunction "B5_B5") (pintype "bidirectional"))
      (node (ref "R2-USB") (pin "1") (pinfunction "1_1") (pintype "passive"))
    )
    (net (code "36") (name "Net-(MCP73831-PROG)") (class "Default")
      (node (ref "MCP73831") (pin "5") (pinfunction "PROG_5") (pintype "input"))
      (node (ref "R2_BAT") (pin "2") (pinfunction "2_2") (pintype "passive"))
    )
    (net (code "37") (name "Net-(MCP73831-STAT)") (class "Default")
      (node (ref "MCP73831") (pin "1") (pinfunction "STAT_1") (pintype "output"))
      (node (ref "R1_BAT") (pin "2") (pinfunction "2_2") (pintype "passive"))
    )
    (net (code "38") (name "Net-(SENSOR2-CSB)") (class "Default")
      (node (ref "SENSOR2") (pin "2") (pinfunction "CSB_2") (pintype "input"))
      (node (ref "SENSOR2") (pin "8") (pinfunction "VDD_8") (pintype "power_in"))
    )
    (net (code "39") (name "PREVGH") (class "Default")
      (node (ref "D5") (pin "1") (pinfunction "K_1") (pintype "bidirectional"))
      (node (ref "EPD_C9") (pin "2") (pinfunction "2_2") (pintype "passive"))
      (node (ref "J1") (pin "21") (pinfunction "21_21") (pintype "bidirectional"))
    )
    (net (code "40") (name "PREVGL") (class "Default")
      (node (ref "D4") (pin "2") (pinfunction "A_2") (pintype "bidirectional"))
      (node (ref "EPD_C11") (pin "2") (pinfunction "2_2") (pintype "passive"))
      (node (ref "J1") (pin "23") (pinfunction "23_23") (pintype "bidirectional"))
    )
    (net (code "41") (name "RESE") (class "Default")
      (node (ref "J1") (pin "3") (pinfunction "3_3") (pintype "bidirectional"))
      (node (ref "Q3") (pin "2") (pinfunction "S_2") (pintype "bidirectional"))
      (node (ref "R3") (pin "2") (pinfunction "2_2") (pintype "passive"))
    )
    (net (code "42") (name "RESE'") (class "Default")
      (node (ref "R2") (pin "2") (pinfunction "2_2") (pintype "passive"))
      (node (ref "R3") (pin "1") (pinfunction "1_1") (pintype "passive"))
      (node (ref "SJ1") (pin "2") (pinfunction "2_2") (pintype "passive"))
    )
    (net (code "43") (name "RESET") (class "Default")
      (node (ref "C5") (pin "1") (pinfunction "1_1") (pintype "passive"))
      (node (ref "IC1") (pin "1") (pinfunction "VOUT_1") (pintype "bidirectional"))
      (node (ref "RESET_BUTTON") (pin "3") (pinfunction "3_3") (pintype "passive"))
      (node (ref "RESET_BUTTON") (pin "4") (pinfunction "4_4") (pintype "passive"))
      (node (ref "R_RESET") (pin "1") (pinfunction "1_1") (pintype "passive"))
      (node (ref "U2") (pin "3") (pinfunction "EN_3") (pintype "input"))
    )
    (net (code "44") (name "RTC_RST") (class "Default")
      (node (ref "U2") (pin "16") (pinfunction "IO18_16") (pintype "bidirectional"))
      (node (ref "U3") (pin "4") (pinfunction "~{RST}_4") (pintype "input"))
    )
    (net (code "45") (name "RX") (class "Default")
      (node (ref "TP2") (pin "TP") (pinfunction "TP_TP") (pintype "input"))
      (node (ref "U2") (pin "24") (pinfunction "RXD0/GPIO17_24") (pintype "bidirectional"))
    )
    (net (code "46") (name "SCK") (class "Default")
      (node (ref "D10") (pin "2") (pinfunction "2_2") (pintype "passive"))
      (node (ref "J1") (pin "13") (pinfunction "13_13") (pintype "bidirectional"))
      (node (ref "J4") (pin "P5") (pinfunction "CLK_P5") (pintype "bidirectional"))
      (node (ref "R6") (pin "1") (pinfunction "1_1") (pintype "passive"))
      (node (ref "TP8") (pin "TP") (pinfunction "TP_TP") (pintype "input"))
      (node (ref "U1") (pin "6") (pinfunction "CLK_6") (pintype "input"))
      (node (ref "U2") (pin "6") (pinfunction "IO6_6") (pintype "bidirectional"))
    )
    (net (code "47") (name "SCL") (class "Default")
      (node (ref "J3") (pin "4") (pinfunction "4_4") (pintype "passive"))
      (node (ref "R2_PINH") (pin "1") (pinfunction "1_1") (pintype "passive"))
      (node (ref "SENSOR2") (pin "4") (pinfunction "SCK_4") (pintype "input"))
      (node (ref "U2") (pin "20") (pinfunction "IO22_20") (pintype "bidirectional"))
      (node (ref "U3") (pin "16") (pinfunction "SCL_16") (pintype "input"))
      (node (ref "U4") (pin "7") (pinfunction "SCL_7") (pintype "input"))
    )
    (net (code "48") (name "SDA") (class "Default")
      (node (ref "J3") (pin "3") (pinfunction "3_3") (pintype "passive"))
      (node (ref "R1_PINH") (pin "1") (pinfunction "1_1") (pintype "passive"))
      (node (ref "SENSOR2") (pin "3") (pinfunction "SDI_3") (pintype "bidirectional"))
      (node (ref "U2") (pin "19") (pinfunction "IO21_19") (pintype "bidirectional"))
      (node (ref "U3") (pin "15") (pinfunction "SDA_15") (pintype "bidirectional"))
      (node (ref "U4") (pin "8") (pinfunction "SDA_8") (pintype "bidirectional"))
    )
    (net (code "49") (name "SRC") (class "Default")
      (node (ref "C4") (pin "2") (pinfunction "2_2") (pintype "passive"))
      (node (ref "D5") (pin "2") (pinfunction "A_2") (pintype "bidirectional"))
      (node (ref "L1") (pin "1") (pinfunction "1_1") (pintype "passive"))
      (node (ref "Q3") (pin "3") (pinfunction "D_3") (pintype "bidirectional"))
    )
    (net (code "50") (name "SS_SD") (class "Default")
      (node (ref "D8") (pin "2") (pinfunction "2_2") (pintype "passive"))
      (node (ref "J4") (pin "P2") (pinfunction "CD/DAT3_P2") (pintype "bidirectional"))
      (node (ref "R10") (pin "1") (pinfunction "1_1") (pintype "passive"))
      (node (ref "U2") (pin "4") (pinfunction "IO4_4") (pintype "bidirectional"))
    )
    (net (code "51") (name "TX") (class "Default")
      (node (ref "TP1") (pin "TP") (pinfunction "TP_TP") (pintype "input"))
      (node (ref "U2") (pin "25") (pinfunction "TXD0/GPIO16_25") (pintype "bidirectional"))
    )
    (net (code "52") (name "USB_D+") (class "Default")
      (node (ref "D1") (pin "1") (pinfunction "I/O1_1_1") (pintype "bidirectional"))
      (node (ref "U2") (pin "14") (pinfunction "IO13_14") (pintype "bidirectional"))
    )
    (net (code "53") (name "USB_D-") (class "Default")
      (node (ref "D1") (pin "3") (pinfunction "I/O2_1_3") (pintype "bidirectional"))
      (node (ref "U2") (pin "13") (pinfunction "IO12_13") (pintype "bidirectional"))
    )
    (net (code "54") (name "VBAT") (class "Default")
      (node (ref "C2_BAT") (pin "1") (pinfunction "1_1") (pintype "passive"))
      (node (ref "MCP73831") (pin "3") (pinfunction "VBAT_3") (pintype "power_in"))
      (node (ref "Q1") (pin "3") (pinfunction "D_3") (pintype "bidirectional"))
      (node (ref "TP3") (pin "TP") (pinfunction "TP_TP") (pintype "input"))
      (node (ref "U4") (pin "2") (pinfunction "CELL_2") (pintype "power_in"))
      (node (ref "U4") (pin "3") (pinfunction "VDD_3") (pintype "power_in"))
    )
    (net (code "55") (name "VBUS") (class "Default")
      (node (ref "C1_BAT") (pin "1") (pinfunction "1_1") (pintype "passive"))
      (node (ref "C4_USB") (pin "1") (pinfunction "1_1") (pintype "passive"))
      (node (ref "C5_USB") (pin "1") (pinfunction "1_1") (pintype "passive"))
      (node (ref "CHG_LED") (pin "A") (pinfunction "A_A") (pintype "passive"))
      (node (ref "D1") (pin "5") (pinfunction "VBUS_5") (pintype "bidirectional"))
      (node (ref "D2") (pin "2") (pinfunction "ANODE_2") (pintype "bidirectional"))
      (node (ref "MCP73831") (pin "4") (pinfunction "VIN_4") (pintype "power_in"))
      (node (ref "PFMF.050.1") (pin "2") (pinfunction "2_2") (pintype "passive"))
      (node (ref "Q1") (pin "1") (pinfunction "G_1") (pintype "bidirectional"))
      (node (ref "R1_PWRUSB") (pin "1") (pinfunction "1_1") (pintype "passive"))
      (node (ref "TP14") (pin "TP") (pinfunction "TP_TP") (pintype "input"))
    )
    (net (code "56") (name "VRTC") (class "Default")
      (node (ref "C10_SUPERCAP") (pin "2") (pinfunction "2_2") (pintype "passive"))
      (node (ref "C8") (pin "1") (pinfunction "1_1") (pintype "passive"))
      (node (ref "R_CAPACITOR") (pin "2") (pinfunction "2_2") (pintype "passive"))
      (node (ref "U3") (pin "14") (pinfunction "VBAT_14") (pintype "power_in"))
    )
    (net (code "57") (name "VUSB") (class "Default")
      (node (ref "J2") (pin "A4") (pinfunction "A4_A4") (pintype "bidirectional"))
      (node (ref "J2") (pin "A9") (pinfunction "A9_A9") (pintype "bidirectional"))
      (node (ref "J2") (pin "B4") (pinfunction "B4_B4") (pintype "bidirectional"))
      (node (ref "J2") (pin "B9") (pinfunction "B9_B9") (pintype "bidirectional"))
      (node (ref "PFMF.050.1") (pin "1") (pinfunction "1_1") (pintype "passive"))
    )
    (net (code "58") (name "unconnected-(EPD_C8-Pad1)") (class "Default")
      (node (ref "EPD_C8") (pin "1") (pinfunction "1_1") (pintype "passive"))
    )
    (net (code "59") (name "unconnected-(IC1-NC-Pad4)") (class "Default")
      (node (ref "IC1") (pin "4") (pinfunction "NC_4") (pintype "no_connect"))
    )
    (net (code "60") (name "unconnected-(IC4-NC-Pad4)") (class "Default")
      (node (ref "IC4") (pin "4") (pinfunction "NC_4") (pintype "no_connect"))
    )
    (net (code "61") (name "unconnected-(J1-Pad1)") (class "Default")
      (node (ref "J1") (pin "1") (pinfunction "1_1") (pintype "bidirectional"))
    )
    (net (code "62") (name "unconnected-(J1-Pad6)") (class "Default")
      (node (ref "J1") (pin "6") (pinfunction "6_6") (pintype "bidirectional"))
    )
    (net (code "63") (name "unconnected-(J1-Pad7)") (class "Default")
      (node (ref "J1") (pin "7") (pinfunction "7_7") (pintype "bidirectional"))
    )
    (net (code "64") (name "unconnected-(J2-PadA8)") (class "Default")
      (node (ref "J2") (pin "A8") (pinfunction "A8_A8") (pintype "bidirectional"))
    )
    (net (code "65") (name "unconnected-(J2-PadB8)") (class "Default")
      (node (ref "J2") (pin "B8") (pinfunction "B8_B8") (pintype "bidirectional"))
    )
    (net (code "66") (name "unconnected-(J4-DAT1-PadP8)") (class "Default")
      (node (ref "J4") (pin "P8") (pinfunction "DAT1_P8") (pintype "bidirectional"))
    )
    (net (code "67") (name "unconnected-(J4-DAT2-PadP1)") (class "Default")
      (node (ref "J4") (pin "P1") (pinfunction "DAT2_P1") (pintype "bidirectional"))
    )
    (net (code "68") (name "unconnected-(J4-DETECTION_1-PadS1)") (class "Default")
      (node (ref "J4") (pin "S1") (pinfunction "DETECTION_1_S1") (pintype "bidirectional"))
    )
    (net (code "69") (name "unconnected-(J4-DETECTION_2-PadS2)") (class "Default")
      (node (ref "J4") (pin "S2") (pinfunction "DETECTION_2_S2") (pintype "bidirectional"))
    )
    (net (code "70") (name "unconnected-(U2-NC-Pad22)") (class "Default")
      (node (ref "U2") (pin "22") (pinfunction "NC_22") (pintype "no_connect"))
    )
    (net (code "71") (name "unconnected-(U4-~{ALERT}-Pad5)") (class "Default")
      (node (ref "U4") (pin "5") (pinfunction "~{ALERT}_5") (pintype "output"))
    )
  )
)
